# DesignSchematic.net
KiCad netlist of a schematic drawn in Altium Designer
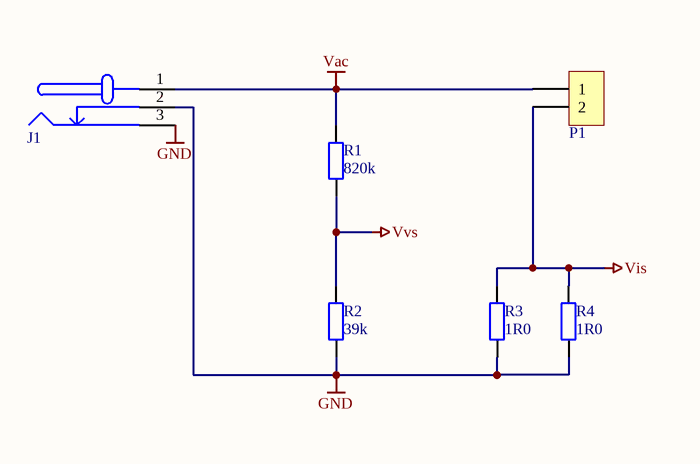
[diagram p0: DesignSchematic.SchDoc]

(export (version "E")
  (design (tool "Eeschema 10.0.6"))
  (components
    (comp (ref "J1")
      (value "DC barrel jack")
      (footprint "AC-Socket")
      (description "DC barrel jack connection to AC source")
      (libsource (lib "EE209_Library") (part "AC_Input"))
    )
    (comp (ref "P1")
      (value "Dual Banana Plugs")
      (footprint "Dual Banana Plug")
      (description "Dual banana plugs connection to the AC load")
      (fields (field (name "PUBLISHER") "Altium Limited"))
      (libsource (lib "EE209_Library") (part "AC_Output"))
    )
    (comp (ref "R1")
      (value "820k")
      (footprint "AXIAL-0.4")
      (description "Through hole resistor")
      (fields (field (name "PUBLISHER") "Altium Limited"))
      (libsource (lib "EE209_Library") (part "Res_TH_0AX4"))
    )
    (comp (ref "R2")
      (value "39k")
      (footprint "AXIAL-0.4")
      (description "Through hole resistor")
      (fields (field (name "PUBLISHER") "Altium Limited"))
      (libsource (lib "EE209_Library") (part "Res_TH_0AX4"))
    )
    (comp (ref "R3")
      (value "1R0")
      (footprint "AXIAL-0.4")
      (description "Through hole resistor")
      (fields (field (name "PUBLISHER") "Altium Limited"))
      (libsource (lib "EE209_Library") (part "Res_TH_0AX4"))
    )
    (comp (ref "R4")
      (value "1R0")
      (footprint "AXIAL-0.4")
      (description "Through hole resistor")
      (fields (field (name "PUBLISHER") "Altium Limited"))
      (libsource (lib "EE209_Library") (part "Res_TH_0AX4"))
    )
  )
  (nets
    (net (code "1") (name "GND") (class "Default")
      (node (ref "J1") (pin "2") (pinfunction "GND_ALT_2") (pintype "power_in"))
      (node (ref "J1") (pin "3") (pinfunction "GND_3") (pintype "power_in"))
      (node (ref "R2") (pin "2") (pinfunction "2_2") (pintype "passive"))
      (node (ref "R3") (pin "2") (pinfunction "2_2") (pintype "passive"))
      (node (ref "R4") (pin "2") (pinfunction "2_2") (pintype "passive"))
    )
    (net (code "2") (name "Vac") (class "Default")
      (node (ref "J1") (pin "1") (pinfunction "VCC_1") (pintype "power_in"))
      (node (ref "P1") (pin "1") (pinfunction "1_1") (pintype "passive"))
      (node (ref "R1") (pin "1") (pinfunction "1_1") (pintype "passive"))
    )
    (net (code "3") (name "Vis") (class "Default")
      (node (ref "P1") (pin "2") (pinfunction "2_2") (pintype "passive"))
      (node (ref "R3") (pin "1") (pinfunction "1_1") (pintype "passive"))
      (node (ref "R4") (pin "1") (pinfunction "1_1") (pintype "passive"))
    )
    (net (code "4") (name "Vvs") (class "Default")
      (node (ref "R1") (pin "2") (pinfunction "2_2") (pintype "passive"))
      (node (ref "R2") (pin "1") (pinfunction "1_1") (pintype "passive"))
    )
  )
)
